# sensors.net
KiCad netlist of a schematic drawn in EAGLE
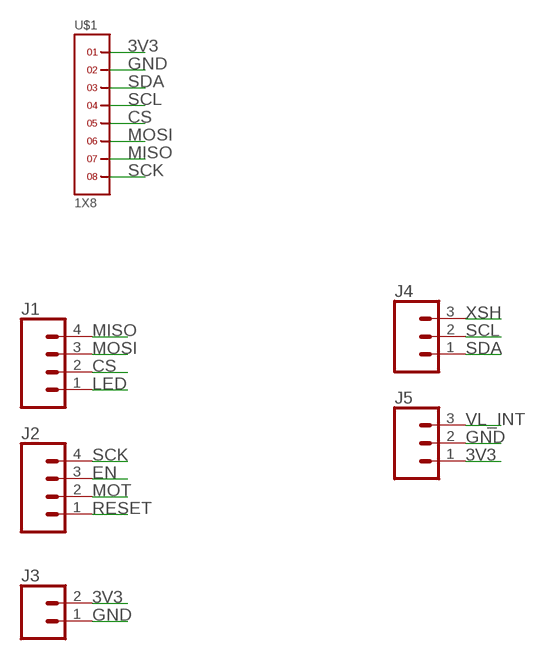
[diagram p0: schematic, sheet 1]

(export (version "E")
  (design (tool "Eeschema 10.0.6"))
  (components
    (comp (ref "J1")
      (value "CONN_041X04_NO_SILK")
      (footprint "eagle-import:1X04_NO_SILK")
      (libsource (lib "eagle-import") (part "CONN_041X04_NO_SILK"))
    )
    (comp (ref "J2")
      (value "CONN_041X04_NO_SILK")
      (footprint "eagle-import:1X04_NO_SILK")
      (libsource (lib "eagle-import") (part "CONN_041X04_NO_SILK"))
    )
    (comp (ref "J3")
      (value "CONN_021X02_NO_SILK")
      (footprint "eagle-import:1X02_NO_SILK")
      (libsource (lib "eagle-import") (part "CONN_021X02_NO_SILK"))
    )
    (comp (ref "J4")
      (value "CONN_031X03_NO_SILK")
      (footprint "eagle-import:1X03_NO_SILK")
      (libsource (lib "eagle-import") (part "CONN_031X03_NO_SILK"))
    )
    (comp (ref "J5")
      (value "CONN_031X03_NO_SILK")
      (footprint "eagle-import:1X03_NO_SILK")
      (libsource (lib "eagle-import") (part "CONN_031X03_NO_SILK"))
    )
    (comp (ref "U$1")
      (value "1X8")
      (footprint "eagle-import:1X8")
      (libsource (lib "eagle-import") (part "1X8"))
    )
  )
  (nets
    (net (code "1") (name "/3V3") (class "Default")
      (node (ref "J3") (pin "2") (pinfunction "2_2") (pintype "passive"))
      (node (ref "J5") (pin "1") (pinfunction "1_1") (pintype "passive"))
      (node (ref "U$1") (pin "1") (pinfunction "1_1") (pintype "bidirectional"))
    )
    (net (code "2") (name "/CS") (class "Default")
      (node (ref "J1") (pin "2") (pinfunction "2_2") (pintype "passive"))
      (node (ref "U$1") (pin "5") (pinfunction "5_5") (pintype "bidirectional"))
    )
    (net (code "3") (name "/EN") (class "Default")
      (node (ref "J2") (pin "3") (pinfunction "3_3") (pintype "passive"))
    )
    (net (code "4") (name "/GND") (class "Default")
      (node (ref "J3") (pin "1") (pinfunction "1_1") (pintype "passive"))
      (node (ref "J5") (pin "2") (pinfunction "2_2") (pintype "passive"))
      (node (ref "U$1") (pin "2") (pinfunction "2_2") (pintype "bidirectional"))
    )
    (net (code "5") (name "/LED") (class "Default")
      (node (ref "J1") (pin "1") (pinfunction "1_1") (pintype "passive"))
    )
    (net (code "6") (name "/MISO") (class "Default")
      (node (ref "J1") (pin "4") (pinfunction "4_4") (pintype "passive"))
      (node (ref "U$1") (pin "7") (pinfunction "7_7") (pintype "bidirectional"))
    )
    (net (code "7") (name "/MOSI") (class "Default")
      (node (ref "J1") (pin "3") (pinfunction "3_3") (pintype "passive"))
      (node (ref "U$1") (pin "6") (pinfunction "6_6") (pintype "bidirectional"))
    )
    (net (code "8") (name "/MOT") (class "Default")
      (node (ref "J2") (pin "2") (pinfunction "2_2") (pintype "passive"))
    )
    (net (code "9") (name "/RESET") (class "Default")
      (node (ref "J2") (pin "1") (pinfunction "1_1") (pintype "passive"))
    )
    (net (code "10") (name "/SCK") (class "Default")
      (node (ref "J2") (pin "4") (pinfunction "4_4") (pintype "passive"))
      (node (ref "U$1") (pin "8") (pinfunction "8_8") (pintype "bidirectional"))
    )
    (net (code "11") (name "/SCL") (class "Default")
      (node (ref "J4") (pin "2") (pinfunction "2_2") (pintype "passive"))
      (node (ref "U$1") (pin "4") (pinfunction "4_4") (pintype "bidirectional"))
    )
    (net (code "12") (name "/SDA") (class "Default")
      (node (ref "J4") (pin "1") (pinfunction "1_1") (pintype "passive"))
      (node (ref "U$1") (pin "3") (pinfunction "3_3") (pintype "bidirectional"))
    )
    (net (code "13") (name "/VL_INT") (class "Default")
      (node (ref "J5") (pin "3") (pinfunction "3_3") (pintype "passive"))
    )
    (net (code "14") (name "/XSH") (class "Default")
      (node (ref "J4") (pin "3") (pinfunction "3_3") (pintype "passive"))
    )
  )
)
